# DC_DC_BOOST_CONVERTER_SOLAR.net
KiCad netlist of a schematic drawn in Altium Designer
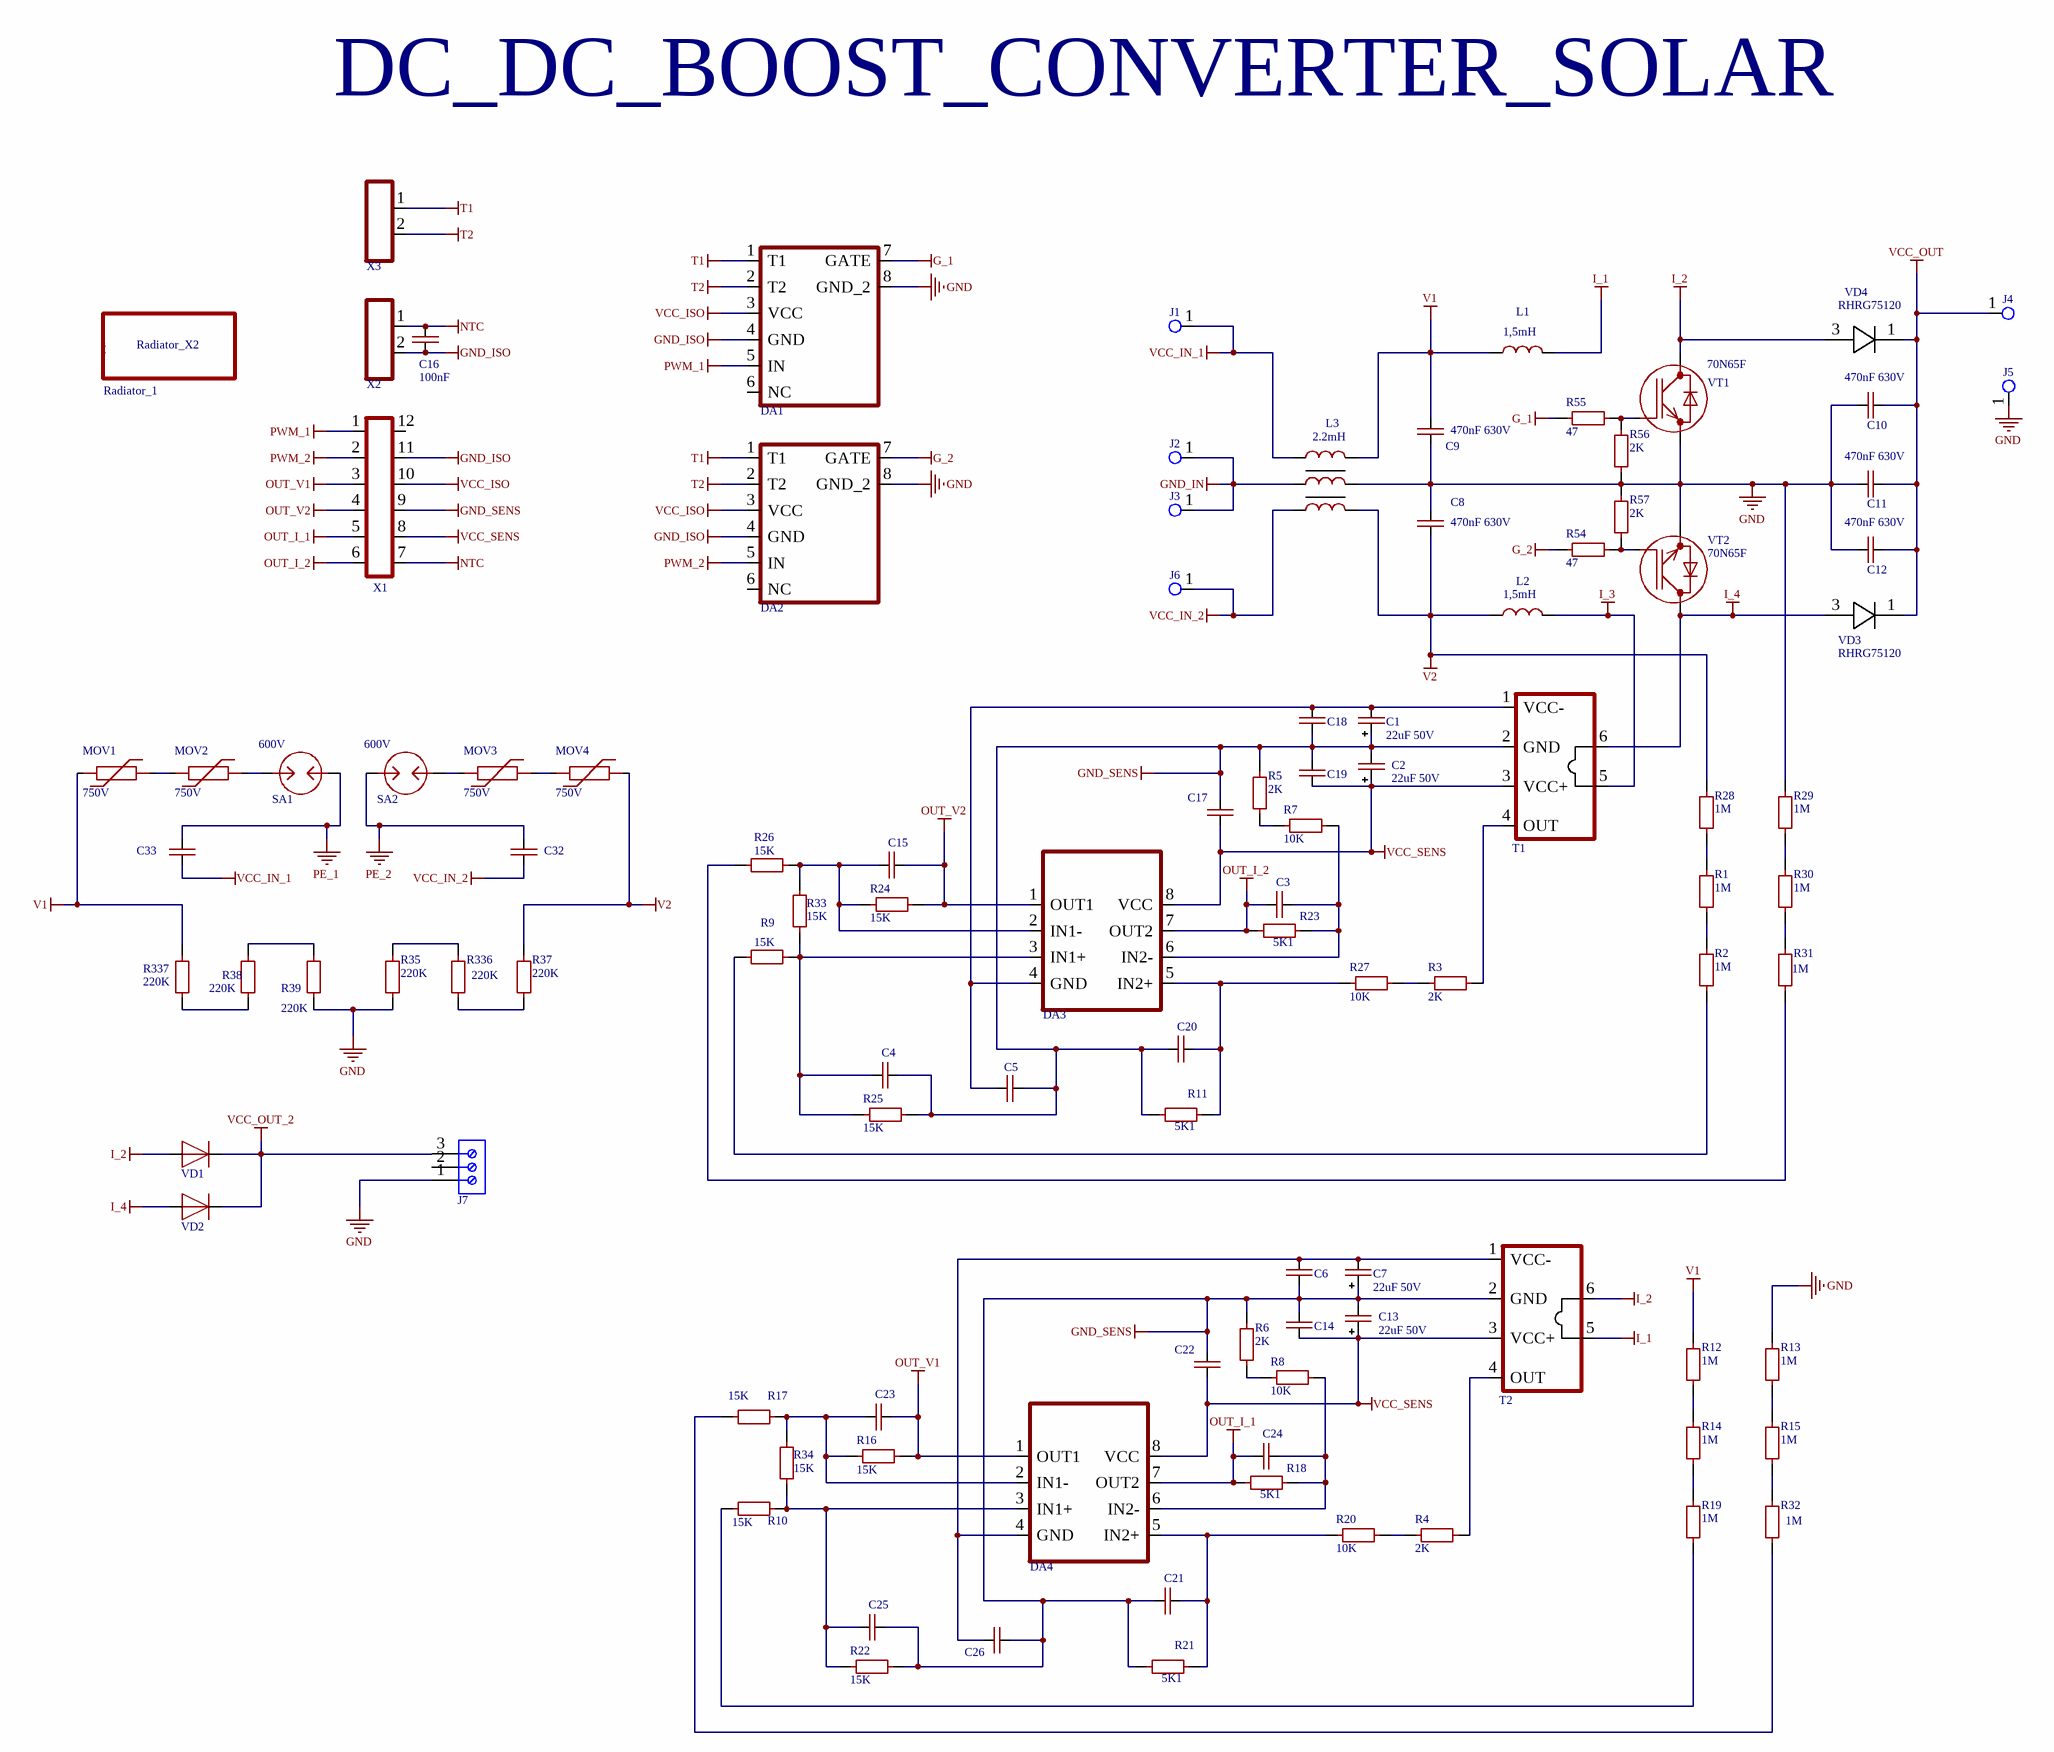
[diagram p0: DC_DC_BOOST_CONVERTER_SOLAR.SchDoc]

(export (version "E")
  (design (tool "Eeschema 10.0.6"))
  (components
    (comp (ref "C1")
      (value "22uF 50V")
      (footprint "CAPPOL_SMD_SIZE_E")
      (libsource (lib "PAS_COMPONENTS") (part "CAP-POLAR"))
    )
    (comp (ref "C2")
      (value "22uF 50V")
      (footprint "CAPPOL_SMD_SIZE_E")
      (libsource (lib "PAS_COMPONENTS") (part "CAP-POLAR"))
    )
    (comp (ref "C3")
      (value "~")
      (footprint "CAP-0805")
      (libsource (lib "PAS_COMPONENTS") (part "CAP-NON-POLAR"))
    )
    (comp (ref "C4")
      (value "~")
      (footprint "CAP-0805")
      (libsource (lib "PAS_COMPONENTS") (part "CAP-NON-POLAR"))
    )
    (comp (ref "C5")
      (value "~")
      (footprint "CAP-0805")
      (libsource (lib "PAS_COMPONENTS") (part "CAP-NON-POLAR"))
    )
    (comp (ref "C6")
      (value "~")
      (footprint "CAP-0805")
      (libsource (lib "PAS_COMPONENTS") (part "CAP-NON-POLAR"))
    )
    (comp (ref "C7")
      (value "22uF 50V")
      (footprint "CAPPOL_SMD_SIZE_E")
      (libsource (lib "PAS_COMPONENTS") (part "CAP-POLAR"))
    )
    (comp (ref "C8")
      (value "470nF 630V")
      (footprint "CAP-FILM-22.5X26.5X10")
      (libsource (lib "PAS_COMPONENTS") (part "CAP-NON-POLAR"))
    )
    (comp (ref "C9")
      (value "470nF 630V")
      (footprint "CAP-FILM-22.5X26.5X10")
      (libsource (lib "PAS_COMPONENTS") (part "CAP-NON-POLAR"))
    )
    (comp (ref "C10")
      (value "470nF 630V")
      (footprint "CAP-FILM-22.5X26.5X10")
      (libsource (lib "PAS_COMPONENTS") (part "CAP-NON-POLAR"))
    )
    (comp (ref "C11")
      (value "470nF 630V")
      (footprint "CAP-FILM-22.5X26.5X10")
      (libsource (lib "PAS_COMPONENTS") (part "CAP-NON-POLAR"))
    )
    (comp (ref "C12")
      (value "470nF 630V")
      (footprint "CAP-FILM-22.5X26.5X10")
      (libsource (lib "PAS_COMPONENTS") (part "CAP-NON-POLAR"))
    )
    (comp (ref "C13")
      (value "22uF 50V")
      (footprint "CAPPOL_SMD_SIZE_E")
      (libsource (lib "PAS_COMPONENTS") (part "CAP-POLAR"))
    )
    (comp (ref "C14")
      (value "~")
      (footprint "CAP-0805")
      (libsource (lib "PAS_COMPONENTS") (part "CAP-NON-POLAR"))
    )
    (comp (ref "C15")
      (value "~")
      (footprint "CAP-0805")
      (libsource (lib "PAS_COMPONENTS") (part "CAP-NON-POLAR"))
    )
    (comp (ref "C16")
      (value "100nF")
      (footprint "CAP-0805")
      (libsource (lib "PAS_COMPONENTS") (part "CAP-NON-POLAR"))
    )
    (comp (ref "C17")
      (value "~")
      (footprint "CAP-0805")
      (libsource (lib "PAS_COMPONENTS") (part "CAP-NON-POLAR"))
    )
    (comp (ref "C18")
      (value "~")
      (footprint "CAP-0805")
      (libsource (lib "PAS_COMPONENTS") (part "CAP-NON-POLAR"))
    )
    (comp (ref "C19")
      (value "~")
      (footprint "CAP-0805")
      (libsource (lib "PAS_COMPONENTS") (part "CAP-NON-POLAR"))
    )
    (comp (ref "C20")
      (value "~")
      (footprint "CAP-0805")
      (libsource (lib "PAS_COMPONENTS") (part "CAP-NON-POLAR"))
    )
    (comp (ref "C21")
      (value "~")
      (footprint "CAP-0805")
      (libsource (lib "PAS_COMPONENTS") (part "CAP-NON-POLAR"))
    )
    (comp (ref "C22")
      (value "~")
      (footprint "CAP-0805")
      (libsource (lib "PAS_COMPONENTS") (part "CAP-NON-POLAR"))
    )
    (comp (ref "C23")
      (value "~")
      (footprint "CAP-0805")
      (libsource (lib "PAS_COMPONENTS") (part "CAP-NON-POLAR"))
    )
    (comp (ref "C24")
      (value "~")
      (footprint "CAP-0805")
      (libsource (lib "PAS_COMPONENTS") (part "CAP-NON-POLAR"))
    )
    (comp (ref "C25")
      (value "~")
      (footprint "CAP-0805")
      (libsource (lib "PAS_COMPONENTS") (part "CAP-NON-POLAR"))
    )
    (comp (ref "C26")
      (value "~")
      (footprint "CAP-0805")
      (libsource (lib "PAS_COMPONENTS") (part "CAP-NON-POLAR"))
    )
    (comp (ref "C32") (value "~") (footprint "CAP-V") (libsource (lib "PASSIVE_COMPONENTS") (part "CAP-V")))
    (comp (ref "C33") (value "~") (footprint "CAP-V") (libsource (lib "PASSIVE_COMPONENTS") (part "CAP-V")))
    (comp (ref "DA1")
      (value "DRIVER_GATE_BOARD_solar_boost_converter")
      (footprint "DRIVER_GATE_BOARD_solar_boost_converter")
      (libsource (lib "DRIVER_GATE_BOARD_solar_boost_converter") (part "DRIVER_GATE_BOARD_solar_boost_converter"))
    )
    (comp (ref "DA2")
      (value "DRIVER_GATE_BOARD_solar_boost_converter")
      (footprint "DRIVER_GATE_BOARD_solar_boost_converter")
      (libsource (lib "DRIVER_GATE_BOARD_solar_boost_converter") (part "DRIVER_GATE_BOARD_solar_boost_converter"))
    )
    (comp (ref "DA3") (value "LM358") (footprint "SOIC8-150") (libsource (lib "LM358") (part "LM358")))
    (comp (ref "DA4") (value "LM358") (footprint "SOIC8-150") (libsource (lib "LM358") (part "LM358")))
    (comp (ref "J1")
      (value "~")
      (footprint "Klema_PCB_15A")
      (libsource (lib "Connectors") (part "Klema_15_A"))
    )
    (comp (ref "J2")
      (value "~")
      (footprint "Klema_PCB_15A")
      (libsource (lib "Connectors") (part "Klema_15_A"))
    )
    (comp (ref "J3")
      (value "~")
      (footprint "Klema_PCB_15A")
      (libsource (lib "Connectors") (part "Klema_15_A"))
    )
    (comp (ref "J4") (value "~") (footprint "Klema_PCB_15A") (libsource (lib "") (part "Klema_15_A_1")))
    (comp (ref "J5")
      (value "~")
      (footprint "Klema_PCB_15A")
      (libsource (lib "Connectors") (part "Klema_15_A"))
    )
    (comp (ref "J6")
      (value "~")
      (footprint "Klema_PCB_15A")
      (libsource (lib "Connectors") (part "Klema_15_A"))
    )
    (comp (ref "J7")
      (value "691101710003")
      (footprint "691101710003")
      (description "WR-TBL Series 101 Horizontal Entry Modular, THT, pitch 5mm, 3p")
      (fields (field (name "MANUFACTURER") "Wurth Elektronik"))
      (libsource (lib "Altium_WR-TBL (rev23d)") (part "691101710003"))
    )
    (comp (ref "L1")
      (value "1,5mH")
      (footprint "DROSSEL_TOR_50X30X20")
      (libsource (lib "DROSSEL_TOR_50X30X20") (part "IND-CONST"))
    )
    (comp (ref "L2")
      (value "1,5mH")
      (footprint "DROSSEL_TOR_50X30X20")
      (libsource (lib "DROSSEL_TOR_50X30X20") (part "IND-CONST"))
    )
    (comp (ref "L3")
      (value "2.2mH")
      (footprint "DROSSEL_TOR_50X30X20X3")
      (libsource (lib "DROSSEL_TOR_50X30X20X3") (part "IND-CONST"))
    )
    (comp (ref "MOV1")
      (value "750V")
      (footprint "VARISTOR_20MM")
      (libsource (lib "VARISTOR") (part "VARISTOR"))
    )
    (comp (ref "MOV2")
      (value "750V")
      (footprint "VARISTOR_20MM")
      (libsource (lib "VARISTOR") (part "VARISTOR"))
    )
    (comp (ref "MOV3")
      (value "750V")
      (footprint "VARISTOR_20MM")
      (libsource (lib "VARISTOR") (part "VARISTOR"))
    )
    (comp (ref "MOV4")
      (value "750V")
      (footprint "VARISTOR_20MM")
      (libsource (lib "VARISTOR") (part "VARISTOR"))
    )
    (comp (ref "R1")
      (value "1M")
      (footprint "RES-1206")
      (libsource (lib "PAS_COMPONENTS") (part "RES-CONST"))
    )
    (comp (ref "R2")
      (value "1M")
      (footprint "RES-1206")
      (libsource (lib "PAS_COMPONENTS") (part "RES-CONST"))
    )
    (comp (ref "R3")
      (value "2K")
      (footprint "RES-0805")
      (libsource (lib "PAS_COMPONENTS") (part "RES-CONST"))
    )
    (comp (ref "R4")
      (value "2K")
      (footprint "RES-0805")
      (libsource (lib "PAS_COMPONENTS") (part "RES-CONST"))
    )
    (comp (ref "R5")
      (value "2K")
      (footprint "RES-0805")
      (libsource (lib "PAS_COMPONENTS") (part "RES-CONST"))
    )
    (comp (ref "R6")
      (value "2K")
      (footprint "RES-0805")
      (libsource (lib "PAS_COMPONENTS") (part "RES-CONST"))
    )
    (comp (ref "R7")
      (value "10K")
      (footprint "RES-0805")
      (libsource (lib "PAS_COMPONENTS") (part "RES-CONST"))
    )
    (comp (ref "R8")
      (value "10K")
      (footprint "RES-0805")
      (libsource (lib "PAS_COMPONENTS") (part "RES-CONST"))
    )
    (comp (ref "R9")
      (value "15K")
      (footprint "RES-0805")
      (libsource (lib "PAS_COMPONENTS") (part "RES-CONST"))
    )
    (comp (ref "R10")
      (value "15K")
      (footprint "RES-0805")
      (libsource (lib "PAS_COMPONENTS") (part "RES-CONST"))
    )
    (comp (ref "R11")
      (value "5K1")
      (footprint "RES-0805")
      (libsource (lib "PAS_COMPONENTS") (part "RES-CONST"))
    )
    (comp (ref "R12")
      (value "1M")
      (footprint "RES-1206")
      (libsource (lib "PAS_COMPONENTS") (part "RES-CONST"))
    )
    (comp (ref "R13")
      (value "1M")
      (footprint "RES-1206")
      (libsource (lib "PAS_COMPONENTS") (part "RES-CONST"))
    )
    (comp (ref "R14")
      (value "1M")
      (footprint "RES-1206")
      (libsource (lib "PAS_COMPONENTS") (part "RES-CONST"))
    )
    (comp (ref "R15")
      (value "1M")
      (footprint "RES-1206")
      (libsource (lib "PAS_COMPONENTS") (part "RES-CONST"))
    )
    (comp (ref "R16")
      (value "15K")
      (footprint "RES-0805")
      (libsource (lib "PAS_COMPONENTS") (part "RES-CONST"))
    )
    (comp (ref "R17")
      (value "15K")
      (footprint "RES-0805")
      (libsource (lib "PAS_COMPONENTS") (part "RES-CONST"))
    )
    (comp (ref "R18")
      (value "5K1")
      (footprint "RES-0805")
      (libsource (lib "PAS_COMPONENTS") (part "RES-CONST"))
    )
    (comp (ref "R19")
      (value "1M")
      (footprint "RES-1206")
      (libsource (lib "PAS_COMPONENTS") (part "RES-CONST"))
    )
    (comp (ref "R20")
      (value "10K")
      (footprint "RES-0805")
      (libsource (lib "PAS_COMPONENTS") (part "RES-CONST"))
    )
    (comp (ref "R21")
      (value "5K1")
      (footprint "RES-0805")
      (libsource (lib "PAS_COMPONENTS") (part "RES-CONST"))
    )
    (comp (ref "R22")
      (value "15K")
      (footprint "RES-0805")
      (libsource (lib "PAS_COMPONENTS") (part "RES-CONST"))
    )
    (comp (ref "R23")
      (value "5K1")
      (footprint "RES-0805")
      (libsource (lib "PAS_COMPONENTS") (part "RES-CONST"))
    )
    (comp (ref "R24")
      (value "15K")
      (footprint "RES-0805")
      (libsource (lib "PAS_COMPONENTS") (part "RES-CONST"))
    )
    (comp (ref "R25")
      (value "15K")
      (footprint "RES-0805")
      (libsource (lib "PAS_COMPONENTS") (part "RES-CONST"))
    )
    (comp (ref "R26")
      (value "15K")
      (footprint "RES-0805")
      (libsource (lib "PAS_COMPONENTS") (part "RES-CONST"))
    )
    (comp (ref "R27")
      (value "10K")
      (footprint "RES-0805")
      (libsource (lib "PAS_COMPONENTS") (part "RES-CONST"))
    )
    (comp (ref "R28")
      (value "1M")
      (footprint "RES-1206")
      (libsource (lib "PAS_COMPONENTS") (part "RES-CONST"))
    )
    (comp (ref "R29")
      (value "1M")
      (footprint "RES-1206")
      (libsource (lib "PAS_COMPONENTS") (part "RES-CONST"))
    )
    (comp (ref "R30")
      (value "1M")
      (footprint "RES-1206")
      (libsource (lib "PAS_COMPONENTS") (part "RES-CONST"))
    )
    (comp (ref "R31")
      (value "1M")
      (footprint "RES-1206")
      (libsource (lib "PAS_COMPONENTS") (part "RES-CONST"))
    )
    (comp (ref "R32")
      (value "1M")
      (footprint "RES-1206")
      (libsource (lib "PAS_COMPONENTS") (part "RES-CONST"))
    )
    (comp (ref "R33")
      (value "15K")
      (footprint "RES-0805")
      (libsource (lib "PAS_COMPONENTS") (part "RES-CONST"))
    )
    (comp (ref "R34")
      (value "15K")
      (footprint "RES-0805")
      (libsource (lib "PAS_COMPONENTS") (part "RES-CONST"))
    )
    (comp (ref "R35")
      (value "220K")
      (footprint "RES-1206")
      (libsource (lib "PAS_COMPONENTS") (part "RES-CONST"))
    )
    (comp (ref "R37")
      (value "220K")
      (footprint "RES-1206")
      (libsource (lib "PAS_COMPONENTS") (part "RES-CONST"))
    )
    (comp (ref "R38")
      (value "220K")
      (footprint "RES-1206")
      (libsource (lib "PAS_COMPONENTS") (part "RES-CONST"))
    )
    (comp (ref "R39")
      (value "220K")
      (footprint "RES-1206")
      (libsource (lib "PAS_COMPONENTS") (part "RES-CONST"))
    )
    (comp (ref "R54")
      (value "47")
      (footprint "RES-1206")
      (libsource (lib "PAS_COMPONENTS") (part "RES-CONST"))
    )
    (comp (ref "R55")
      (value "47")
      (footprint "RES-1206")
      (libsource (lib "PAS_COMPONENTS") (part "RES-CONST"))
    )
    (comp (ref "R56")
      (value "2K")
      (footprint "RES-1206")
      (libsource (lib "PAS_COMPONENTS") (part "RES-CONST"))
    )
    (comp (ref "R57")
      (value "2K")
      (footprint "RES-1206")
      (libsource (lib "PAS_COMPONENTS") (part "RES-CONST"))
    )
    (comp (ref "R336")
      (value "220K")
      (footprint "RES-1206")
      (libsource (lib "PAS_COMPONENTS") (part "RES-CONST"))
    )
    (comp (ref "R337")
      (value "220K")
      (footprint "RES-1206")
      (libsource (lib "PAS_COMPONENTS") (part "RES-CONST"))
    )
    (comp (ref "Radiator_1")
      (value "Radiator_X2")
      (footprint "Radiator_X2")
      (libsource (lib "Radiator_X2") (part "Radiator_X2"))
    )
    (comp (ref "SA1") (value "600V") (footprint "SPARK_GAP") (libsource (lib "SPARK_GAP") (part "SPARK_GAP")))
    (comp (ref "SA2") (value "600V") (footprint "SPARK_GAP") (libsource (lib "SPARK_GAP") (part "SPARK_GAP")))
    (comp (ref "T1")
      (value "STB-HAA20")
      (footprint "STB-HAA20")
      (libsource (lib "STB-HAA20") (part "STB-HAA20"))
    )
    (comp (ref "T2")
      (value "STB-HAA20")
      (footprint "STB-HAA20")
      (libsource (lib "STB-HAA20") (part "STB-HAA20"))
    )
    (comp (ref "VD1") (value "DIODE") (footprint "DIODE_R6") (libsource (lib "DIODE_R6") (part "DIODE")))
    (comp (ref "VD2") (value "DIODE") (footprint "DIODE_R6") (libsource (lib "DIODE_R6") (part "DIODE")))
    (comp (ref "VD3") (value "RHRG75120") (footprint "TO-247-2") (libsource (lib "Diodes") (part "MUR4060")))
    (comp (ref "VD4") (value "RHRG75120") (footprint "TO-247-2") (libsource (lib "Diodes") (part "MUR4060")))
    (comp (ref "VT1")
      (value "70N65F")
      (footprint "TO-247-3")
      (libsource (lib "TRANSISTORS") (part "IGBT-N-GCE"))
    )
    (comp (ref "VT2")
      (value "70N65F")
      (footprint "TO-247-3")
      (libsource (lib "TRANSISTORS") (part "IGBT-N-GCE"))
    )
    (comp (ref "X1")
      (value "CONN_IDC_12_PIN2.54")
      (footprint "CONN_IDC_12_PIN2.54")
      (libsource (lib "CONN_IDC_12_PIN2.54") (part "CONN_IDC_12_PIN2.54"))
    )
    (comp (ref "X2") (value "CONN-2-PIN") (footprint "XH2-") (libsource (lib "XH 2PIN") (part "CONN-2-PIN")))
    (comp (ref "X3") (value "CONN-2-PIN") (footprint "XH2-") (libsource (lib "XH 2PIN") (part "CONN-2-PIN")))
  )
  (nets
    (net (code "1") (name "GND") (class "Default")
      (node (ref "C10") (pin "1") (pinfunction "1_1") (pintype "passive"))
      (node (ref "C11") (pin "1") (pinfunction "1_1") (pintype "passive"))
      (node (ref "C12") (pin "1") (pinfunction "1_1") (pintype "passive"))
      (node (ref "C8") (pin "1") (pinfunction "1_1") (pintype "passive"))
      (node (ref "C9") (pin "2") (pinfunction "2_2") (pintype "passive"))
      (node (ref "DA1") (pin "8") (pinfunction "GND_2_8") (pintype "passive"))
      (node (ref "DA2") (pin "8") (pinfunction "GND_2_8") (pintype "passive"))
      (node (ref "J5") (pin "1") (pinfunction "0_1") (pintype "passive"))
      (node (ref "J7") (pin "1") (pinfunction "1_1") (pintype "passive"))
      (node (ref "L3") (pin "4") (pinfunction "4_4") (pintype "passive"))
      (node (ref "R13") (pin "1") (pinfunction "1_1") (pintype "passive"))
      (node (ref "R29") (pin "1") (pinfunction "1_1") (pintype "passive"))
      (node (ref "R35") (pin "2") (pinfunction "2_2") (pintype "passive"))
      (node (ref "R39") (pin "2") (pinfunction "2_2") (pintype "passive"))
      (node (ref "R56") (pin "2") (pinfunction "2_2") (pintype "passive"))
      (node (ref "R57") (pin "1") (pinfunction "1_1") (pintype "passive"))
      (node (ref "VT1") (pin "3") (pinfunction "E_3") (pintype "passive"))
      (node (ref "VT2") (pin "3") (pinfunction "E_3") (pintype "passive"))
    )
    (net (code "2") (name "GND_IN") (class "Default")
      (node (ref "J2") (pin "1") (pinfunction "0_1") (pintype "passive"))
      (node (ref "J3") (pin "1") (pinfunction "0_1") (pintype "passive"))
      (node (ref "L3") (pin "3") (pinfunction "3_3") (pintype "passive"))
    )
    (net (code "3") (name "GND_ISO") (class "Default")
      (node (ref "C16") (pin "2") (pinfunction "2_2") (pintype "passive"))
      (node (ref "DA1") (pin "4") (pinfunction "GND_4") (pintype "passive"))
      (node (ref "DA2") (pin "4") (pinfunction "GND_4") (pintype "passive"))
      (node (ref "X1") (pin "11") (pinfunction "11_11") (pintype "passive"))
      (node (ref "X2") (pin "2") (pinfunction "2_2") (pintype "passive"))
    )
    (net (code "4") (name "GND_SENS") (class "Default")
      (node (ref "C1") (pin "1") (pinfunction "+_1") (pintype "passive"))
      (node (ref "C13") (pin "2") (pinfunction "-_2") (pintype "passive"))
      (node (ref "C14") (pin "2") (pinfunction "2_2") (pintype "passive"))
      (node (ref "C17") (pin "2") (pinfunction "2_2") (pintype "passive"))
      (node (ref "C18") (pin "1") (pinfunction "1_1") (pintype "passive"))
      (node (ref "C19") (pin "2") (pinfunction "2_2") (pintype "passive"))
      (node (ref "C2") (pin "2") (pinfunction "-_2") (pintype "passive"))
      (node (ref "C20") (pin "1") (pinfunction "1_1") (pintype "passive"))
      (node (ref "C21") (pin "1") (pinfunction "1_1") (pintype "passive"))
      (node (ref "C22") (pin "2") (pinfunction "2_2") (pintype "passive"))
      (node (ref "C25") (pin "1") (pinfunction "1_1") (pintype "passive"))
      (node (ref "C26") (pin "2") (pinfunction "2_2") (pintype "passive"))
      (node (ref "C4") (pin "1") (pinfunction "1_1") (pintype "passive"))
      (node (ref "C5") (pin "2") (pinfunction "2_2") (pintype "passive"))
      (node (ref "C6") (pin "1") (pinfunction "1_1") (pintype "passive"))
      (node (ref "C7") (pin "1") (pinfunction "+_1") (pintype "passive"))
      (node (ref "R11") (pin "1") (pinfunction "1_1") (pintype "passive"))
      (node (ref "R21") (pin "1") (pinfunction "1_1") (pintype "passive"))
      (node (ref "R22") (pin "2") (pinfunction "2_2") (pintype "passive"))
      (node (ref "R25") (pin "2") (pinfunction "2_2") (pintype "passive"))
      (node (ref "R5") (pin "1") (pinfunction "1_1") (pintype "passive"))
      (node (ref "R6") (pin "1") (pinfunction "1_1") (pintype "passive"))
      (node (ref "T1") (pin "2") (pinfunction "GND_2") (pintype "passive"))
      (node (ref "T2") (pin "2") (pinfunction "GND_2") (pintype "passive"))
      (node (ref "X1") (pin "9") (pinfunction "9_9") (pintype "passive"))
    )
    (net (code "5") (name "G_1") (class "Default")
      (node (ref "DA1") (pin "7") (pinfunction "GATE_7") (pintype "passive"))
      (node (ref "R55") (pin "2") (pinfunction "2_2") (pintype "passive"))
    )
    (net (code "6") (name "G_2") (class "Default")
      (node (ref "DA2") (pin "7") (pinfunction "GATE_7") (pintype "passive"))
      (node (ref "R54") (pin "2") (pinfunction "2_2") (pintype "passive"))
    )
    (net (code "7") (name "I_1") (class "Default")
      (node (ref "L1") (pin "2") (pinfunction "2_2") (pintype "passive"))
      (node (ref "T2") (pin "5") (pintype "passive"))
    )
    (net (code "8") (name "I_2") (class "Default")
      (node (ref "T2") (pin "6") (pintype "passive"))
      (node (ref "VD1") (pin "2") (pinfunction "A_2") (pintype "passive"))
      (node (ref "VD4") (pin "3") (pinfunction "3_3") (pintype "passive"))
      (node (ref "VT1") (pin "2") (pinfunction "C_2") (pintype "passive"))
    )
    (net (code "9") (name "I_3") (class "Default")
      (node (ref "L2") (pin "2") (pinfunction "2_2") (pintype "passive"))
      (node (ref "T1") (pin "5") (pintype "passive"))
    )
    (net (code "10") (name "I_4") (class "Default")
      (node (ref "T1") (pin "6") (pintype "passive"))
      (node (ref "VD2") (pin "2") (pinfunction "A_2") (pintype "passive"))
      (node (ref "VD3") (pin "3") (pinfunction "3_3") (pintype "passive"))
      (node (ref "VT2") (pin "2") (pinfunction "C_2") (pintype "passive"))
    )
    (net (code "11") (name "NTC") (class "Default")
      (node (ref "C16") (pin "1") (pinfunction "1_1") (pintype "passive"))
      (node (ref "X1") (pin "7") (pinfunction "7_7") (pintype "passive"))
      (node (ref "X2") (pin "1") (pinfunction "1_1") (pintype "passive"))
    )
    (net (code "12") (name "Net-(C1--)") (class "Default")
      (node (ref "C1") (pin "2") (pinfunction "-_2") (pintype "passive"))
      (node (ref "C18") (pin "2") (pinfunction "2_2") (pintype "passive"))
      (node (ref "C5") (pin "1") (pinfunction "1_1") (pintype "passive"))
      (node (ref "DA3") (pin "4") (pinfunction "GND_4") (pintype "passive"))
      (node (ref "T1") (pin "1") (pinfunction "VCC-_1") (pintype "passive"))
    )
    (net (code "13") (name "Net-(C7--)") (class "Default")
      (node (ref "C26") (pin "1") (pinfunction "1_1") (pintype "passive"))
      (node (ref "C6") (pin "2") (pinfunction "2_2") (pintype "passive"))
      (node (ref "C7") (pin "2") (pinfunction "-_2") (pintype "passive"))
      (node (ref "DA4") (pin "4") (pinfunction "GND_4") (pintype "passive"))
      (node (ref "T2") (pin "1") (pinfunction "VCC-_1") (pintype "passive"))
    )
    (net (code "14") (name "Net-(DA3-IN1+)") (class "Default")
      (node (ref "C4") (pin "2") (pinfunction "2_2") (pintype "passive"))
      (node (ref "DA3") (pin "3") (pinfunction "IN1+_3") (pintype "passive"))
      (node (ref "R25") (pin "1") (pinfunction "1_1") (pintype "passive"))
      (node (ref "R33") (pin "1") (pinfunction "1_1") (pintype "passive"))
      (node (ref "R9") (pin "1") (pinfunction "1_1") (pintype "passive"))
    )
    (net (code "15") (name "Net-(DA3-IN1-)") (class "Default")
      (node (ref "C15") (pin "2") (pinfunction "2_2") (pintype "passive"))
      (node (ref "DA3") (pin "2") (pinfunction "IN1-_2") (pintype "passive"))
      (node (ref "R24") (pin "1") (pinfunction "1_1") (pintype "passive"))
      (node (ref "R26") (pin "1") (pinfunction "1_1") (pintype "passive"))
      (node (ref "R33") (pin "2") (pinfunction "2_2") (pintype "passive"))
    )
    (net (code "16") (name "Net-(DA3-IN2+)") (class "Default")
      (node (ref "C20") (pin "2") (pinfunction "2_2") (pintype "passive"))
      (node (ref "DA3") (pin "5") (pinfunction "IN2+_5") (pintype "passive"))
      (node (ref "R11") (pin "2") (pinfunction "2_2") (pintype "passive"))
      (node (ref "R27") (pin "2") (pinfunction "2_2") (pintype "passive"))
    )
    (net (code "17") (name "Net-(DA3-IN2-)") (class "Default")
      (node (ref "C3") (pin "1") (pinfunction "1_1") (pintype "passive"))
      (node (ref "DA3") (pin "6") (pinfunction "IN2-_6") (pintype "passive"))
      (node (ref "R23") (pin "2") (pinfunction "2_2") (pintype "passive"))
      (node (ref "R7") (pin "2") (pinfunction "2_2") (pintype "passive"))
    )
    (net (code "18") (name "Net-(DA4-IN1+)") (class "Default")
      (node (ref "C25") (pin "2") (pinfunction "2_2") (pintype "passive"))
      (node (ref "DA4") (pin "3") (pinfunction "IN1+_3") (pintype "passive"))
      (node (ref "R10") (pin "1") (pinfunction "1_1") (pintype "passive"))
      (node (ref "R22") (pin "1") (pinfunction "1_1") (pintype "passive"))
      (node (ref "R34") (pin "1") (pinfunction "1_1") (pintype "passive"))
    )
    (net (code "19") (name "Net-(DA4-IN1-)") (class "Default")
      (node (ref "C23") (pin "2") (pinfunction "2_2") (pintype "passive"))
      (node (ref "DA4") (pin "2") (pinfunction "IN1-_2") (pintype "passive"))
      (node (ref "R16") (pin "1") (pinfunction "1_1") (pintype "passive"))
      (node (ref "R17") (pin "1") (pinfunction "1_1") (pintype "passive"))
      (node (ref "R34") (pin "2") (pinfunction "2_2") (pintype "passive"))
    )
    (net (code "20") (name "Net-(DA4-IN2+)") (class "Default")
      (node (ref "C21") (pin "2") (pinfunction "2_2") (pintype "passive"))
      (node (ref "DA4") (pin "5") (pinfunction "IN2+_5") (pintype "passive"))
      (node (ref "R20") (pin "2") (pinfunction "2_2") (pintype "passive"))
      (node (ref "R21") (pin "2") (pinfunction "2_2") (pintype "passive"))
    )
    (net (code "21") (name "Net-(DA4-IN2-)") (class "Default")
      (node (ref "C24") (pin "1") (pinfunction "1_1") (pintype "passive"))
      (node (ref "DA4") (pin "6") (pinfunction "IN2-_6") (pintype "passive"))
      (node (ref "R18") (pin "2") (pinfunction "2_2") (pintype "passive"))
      (node (ref "R8") (pin "2") (pinfunction "2_2") (pintype "passive"))
    )
    (net (code "22") (name "Net-(MOV1-Pad2)") (class "Default")
      (node (ref "MOV1") (pin "2") (pinfunction "2_2") (pintype "passive"))
      (node (ref "MOV2") (pin "1") (pinfunction "1_1") (pintype "passive"))
    )
    (net (code "23") (name "Net-(MOV2-Pad2)") (class "Default")
      (node (ref "MOV2") (pin "2") (pinfunction "2_2") (pintype "passive"))
      (node (ref "SA1") (pin "1") (pinfunction "1_1") (pintype "passive"))
    )
    (net (code "24") (name "Net-(MOV3-Pad1)") (class "Default")
      (node (ref "MOV3") (pin "1") (pinfunction "1_1") (pintype "passive"))
      (node (ref "SA2") (pin "2") (pinfunction "2_2") (pintype "passive"))
    )
    (net (code "25") (name "Net-(MOV3-Pad2)") (class "Default")
      (node (ref "MOV3") (pin "2") (pinfunction "2_2") (pintype "passive"))
      (node (ref "MOV4") (pin "1") (pinfunction "1_1") (pintype "passive"))
    )
    (net (code "26") (name "Net-(R1-Pad1)") (class "Default")
      (node (ref "R1") (pin "1") (pinfunction "1_1") (pintype "passive"))
      (node (ref "R28") (pin "2") (pinfunction "2_2") (pintype "passive"))
    )
    (net (code "27") (name "Net-(R1-Pad2)") (class "Default")
      (node (ref "R1") (pin "2") (pinfunction "2_2") (pintype "passive"))
      (node (ref "R2") (pin "1") (pinfunction "1_1") (pintype "passive"))
    )
    (net (code "28") (name "Net-(R2-Pad2)") (class "Default")
      (node (ref "R2") (pin "2") (pinfunction "2_2") (pintype "passive"))
      (node (ref "R9") (pin "2") (pinfunction "2_2") (pintype "passive"))
    )
    (net (code "29") (name "Net-(R5-Pad2)") (class "Default")
      (node (ref "R5") (pin "2") (pinfunction "2_2") (pintype "passive"))
      (node (ref "R7") (pin "1") (pinfunction "1_1") (pintype "passive"))
    )
    (net (code "30") (name "Net-(R6-Pad2)") (class "Default")
      (node (ref "R6") (pin "2") (pinfunction "2_2") (pintype "passive"))
      (node (ref "R8") (pin "1") (pinfunction "1_1") (pintype "passive"))
    )
    (net (code "31") (name "Net-(R10-Pad2)") (class "Default")
      (node (ref "R10") (pin "2") (pinfunction "2_2") (pintype "passive"))
      (node (ref "R19") (pin "2") (pinfunction "2_2") (pintype "passive"))
    )
    (net (code "32") (name "Net-(R12-Pad2)") (class "Default")
      (node (ref "R12") (pin "2") (pinfunction "2_2") (pintype "passive"))
      (node (ref "R14") (pin "1") (pinfunction "1_1") (pintype "passive"))
    )
    (net (code "33") (name "Net-(R13-Pad2)") (class "Default")
      (node (ref "R13") (pin "2") (pinfunction "2_2") (pintype "passive"))
      (node (ref "R15") (pin "1") (pinfunction "1_1") (pintype "passive"))
    )
    (net (code "34") (name "Net-(R14-Pad2)") (class "Default")
      (node (ref "R14") (pin "2") (pinfunction "2_2") (pintype "passive"))
      (node (ref "R19") (pin "1") (pinfunction "1_1") (pintype "passive"))
    )
    (net (code "35") (name "Net-(R15-Pad2)") (class "Default")
      (node (ref "R15") (pin "2") (pinfunction "2_2") (pintype "passive"))
      (node (ref "R32") (pin "1") (pinfunction "1_1") (pintype "passive"))
    )
    (net (code "36") (name "Net-(R17-Pad2)") (class "Default")
      (node (ref "R17") (pin "2") (pinfunction "2_2") (pintype "passive"))
      (node (ref "R32") (pin "2") (pinfunction "2_2") (pintype "passive"))
    )
    (net (code "37") (name "Net-(R20-Pad1)") (class "Default")
      (node (ref "R20") (pin "1") (pinfunction "1_1") (pintype "passive"))
      (node (ref "R4") (pin "2") (pinfunction "2_2") (pintype "passive"))
    )
    (net (code "38") (name "Net-(R26-Pad2)") (class "Default")
      (node (ref "R26") (pin "2") (pinfunction "2_2") (pintype "passive"))
      (node (ref "R31") (pin "2") (pinfunction "2_2") (pintype "passive"))
    )
    (net (code "39") (name "Net-(R27-Pad1)") (class "Default")
      (node (ref "R27") (pin "1") (pinfunction "1_1") (pintype "passive"))
      (node (ref "R3") (pin "2") (pinfunction "2_2") (pintype "passive"))
    )
    (net (code "40") (name "Net-(R29-Pad2)") (class "Default")
      (node (ref "R29") (pin "2") (pinfunction "2_2") (pintype "passive"))
      (node (ref "R30") (pin "1") (pinfunction "1_1") (pintype "passive"))
    )
    (net (code "41") (name "Net-(R30-Pad2)") (class "Default")
      (node (ref "R30") (pin "2") (pinfunction "2_2") (pintype "passive"))
      (node (ref "R31") (pin "1") (pinfunction "1_1") (pintype "passive"))
    )
    (net (code "42") (name "Net-(R38-Pad1)") (class "Default")
      (node (ref "R38") (pin "1") (pinfunction "1_1") (pintype "passive"))
      (node (ref "R39") (pin "1") (pinfunction "1_1") (pintype "passive"))
    )
    (net (code "43") (name "Net-(R336-Pad1)") (class "Default")
      (node (ref "R336") (pin "1") (pinfunction "1_1") (pintype "passive"))
      (node (ref "R35") (pin "1") (pinfunction "1_1") (pintype "passive"))
    )
    (net (code "44") (name "Net-(R336-Pad2)") (class "Default")
      (node (ref "R336") (pin "2") (pinfunction "2_2") (pintype "passive"))
      (node (ref "R37") (pin "2") (pinfunction "2_2") (pintype "passive"))
    )
    (net (code "45") (name "Net-(R337-Pad2)") (class "Default")
      (node (ref "R337") (pin "2") (pinfunction "2_2") (pintype "passive"))
      (node (ref "R38") (pin "2") (pinfunction "2_2") (pintype "passive"))
    )
    (net (code "46") (name "Net-(T1-OUT)") (class "Default")
      (node (ref "R3") (pin "1") (pinfunction "1_1") (pintype "passive"))
      (node (ref "T1") (pin "4") (pinfunction "OUT_4") (pintype "passive"))
    )
    (net (code "47") (name "Net-(T2-OUT)") (class "Default")
      (node (ref "R4") (pin "1") (pinfunction "1_1") (pintype "passive"))
      (node (ref "T2") (pin "4") (pinfunction "OUT_4") (pintype "passive"))
    )
    (net (code "48") (name "Net-(VT1-G)") (class "Default")
      (node (ref "R55") (pin "1") (pinfunction "1_1") (pintype "passive"))
      (node (ref "R56") (pin "1") (pinfunction "1_1") (pintype "passive"))
      (node (ref "VT1") (pin "1") (pinfunction "G_1") (pintype "passive"))
    )
    (net (code "49") (name "Net-(VT2-G)") (class "Default")
      (node (ref "R54") (pin "1") (pinfunction "1_1") (pintype "passive"))
      (node (ref "R57") (pin "2") (pinfunction "2_2") (pintype "passive"))
      (node (ref "VT2") (pin "1") (pinfunction "G_1") (pintype "passive"))
    )
    (net (code "50") (name "OUT_I_1") (class "Default")
      (node (ref "C24") (pin "2") (pinfunction "2_2") (pintype "passive"))
      (node (ref "DA4") (pin "7") (pinfunction "OUT2_7") (pintype "passive"))
      (node (ref "R18") (pin "1") (pinfunction "1_1") (pintype "passive"))
      (node (ref "X1") (pin "5") (pinfunction "5_5") (pintype "passive"))
    )
    (net (code "51") (name "OUT_I_2") (class "Default")
      (node (ref "C3") (pin "2") (pinfunction "2_2") (pintype "passive"))
      (node (ref "DA3") (pin "7") (pinfunction "OUT2_7") (pintype "passive"))
      (node (ref "R23") (pin "1") (pinfunction "1_1") (pintype "passive"))
      (node (ref "X1") (pin "6") (pinfunction "6_6") (pintype "passive"))
    )
    (net (code "52") (name "OUT_V1") (class "Default")
      (node (ref "C23") (pin "1") (pinfunction "1_1") (pintype "passive"))
      (node (ref "DA4") (pin "1") (pinfunction "OUT1_1") (pintype "passive"))
      (node (ref "R16") (pin "2") (pinfunction "2_2") (pintype "passive"))
      (node (ref "X1") (pin "3") (pinfunction "3_3") (pintype "passive"))
    )
    (net (code "53") (name "OUT_V2") (class "Default")
      (node (ref "C15") (pin "1") (pinfunction "1_1") (pintype "passive"))
      (node (ref "DA3") (pin "1") (pinfunction "OUT1_1") (pintype "passive"))
      (node (ref "R24") (pin "2") (pinfunction "2_2") (pintype "passive"))
      (node (ref "X1") (pin "4") (pinfunction "4_4") (pintype "passive"))
    )
    (net (code "54") (name "PE_1") (class "Default")
      (node (ref "C33") (pin "1") (pinfunction "1_1") (pintype "passive"))
      (node (ref "SA1") (pin "2") (pinfunction "2_2") (pintype "passive"))
    )
    (net (code "55") (name "PE_2") (class "Default")
      (node (ref "C32") (pin "2") (pinfunction "2_2") (pintype "passive"))
      (node (ref "SA2") (pin "1") (pinfunction "1_1") (pintype "passive"))
    )
    (net (code "56") (name "PWM_1") (class "Default")
      (node (ref "DA1") (pin "5") (pinfunction "IN_5") (pintype "passive"))
      (node (ref "X1") (pin "1") (pinfunction "1_1") (pintype "passive"))
    )
    (net (code "57") (name "PWM_2") (class "Default")
      (node (ref "DA2") (pin "5") (pinfunction "IN_5") (pintype "passive"))
      (node (ref "X1") (pin "2") (pinfunction "2_2") (pintype "passive"))
    )
    (net (code "58") (name "T1") (class "Default")
      (node (ref "DA1") (pin "1") (pinfunction "T1_1") (pintype "passive"))
      (node (ref "DA2") (pin "1") (pinfunction "T1_1") (pintype "passive"))
      (node (ref "X3") (pin "1") (pinfunction "1_1") (pintype "passive"))
    )
    (net (code "59") (name "T2") (class "Default")
      (node (ref "DA1") (pin "2") (pinfunction "T2_2") (pintype "passive"))
      (node (ref "DA2") (pin "2") (pinfunction "T2_2") (pintype "passive"))
      (node (ref "X3") (pin "2") (pinfunction "2_2") (pintype "passive"))
    )
    (net (code "60") (name "V1") (class "Default")
      (node (ref "C9") (pin "1") (pinfunction "1_1") (pintype "passive"))
      (node (ref "L1") (pin "1") (pinfunction "1_1") (pintype "passive"))
      (node (ref "L3") (pin "2") (pinfunction "2_2") (pintype "passive"))
      (node (ref "MOV1") (pin "1") (pinfunction "1_1") (pintype "passive"))
      (node (ref "R12") (pin "1") (pinfunction "1_1") (pintype "passive"))
      (node (ref "R337") (pin "1") (pinfunction "1_1") (pintype "passive"))
    )
    (net (code "61") (name "V2") (class "Default")
      (node (ref "C8") (pin "2") (pinfunction "2_2") (pintype "passive"))
      (node (ref "L2") (pin "1") (pinfunction "1_1") (pintype "passive"))
      (node (ref "L3") (pin "6") (pinfunction "6_6") (pintype "passive"))
      (node (ref "MOV4") (pin "2") (pinfunction "2_2") (pintype "passive"))
      (node (ref "R28") (pin "1") (pinfunction "1_1") (pintype "passive"))
      (node (ref "R37") (pin "1") (pinfunction "1_1") (pintype "passive"))
    )
    (net (code "62") (name "VCC_IN_1") (class "Default")
      (node (ref "C33") (pin "2") (pinfunction "2_2") (pintype "passive"))
      (node (ref "J1") (pin "1") (pinfunction "0_1") (pintype "passive"))
      (node (ref "L3") (pin "1") (pinfunction "1_1") (pintype "passive"))
    )
    (net (code "63") (name "VCC_IN_2") (class "Default")
      (node (ref "C32") (pin "1") (pinfunction "1_1") (pintype "passive"))
      (node (ref "J6") (pin "1") (pinfunction "0_1") (pintype "passive"))
      (node (ref "L3") (pin "5") (pinfunction "5_5") (pintype "passive"))
    )
    (net (code "64") (name "VCC_ISO") (class "Default")
      (node (ref "DA1") (pin "3") (pinfunction "VCC_3") (pintype "passive"))
      (node (ref "DA2") (pin "3") (pinfunction "VCC_3") (pintype "passive"))
      (node (ref "X1") (pin "10") (pinfunction "10_10") (pintype "passive"))
    )
    (net (code "65") (name "VCC_OUT") (class "Default")
      (node (ref "C10") (pin "2") (pinfunction "2_2") (pintype "passive"))
      (node (ref "C11") (pin "2") (pinfunction "2_2") (pintype "passive"))
      (node (ref "C12") (pin "2") (pinfunction "2_2") (pintype "passive"))
      (node (ref "J4") (pin "1") (pinfunction "0_1") (pintype "passive"))
      (node (ref "VD3") (pin "1") (pinfunction "1_1") (pintype "passive"))
      (node (ref "VD4") (pin "1") (pinfunction "1_1") (pintype "passive"))
    )
    (net (code "66") (name "VCC_OUT_2") (class "Default")
      (node (ref "J7") (pin "3") (pinfunction "3_3") (pintype "passive"))
      (node (ref "VD1") (pin "1") (pinfunction "C_1") (pintype "passive"))
      (node (ref "VD2") (pin "1") (pinfunction "C_1") (pintype "passive"))
    )
    (net (code "67") (name "VCC_SENS") (class "Default")
      (node (ref "C13") (pin "1") (pinfunction "+_1") (pintype "passive"))
      (node (ref "C14") (pin "1") (pinfunction "1_1") (pintype "passive"))
      (node (ref "C17") (pin "1") (pinfunction "1_1") (pintype "passive"))
      (node (ref "C19") (pin "1") (pinfunction "1_1") (pintype "passive"))
      (node (ref "C2") (pin "1") (pinfunction "+_1") (pintype "passive"))
      (node (ref "C22") (pin "1") (pinfunction "1_1") (pintype "passive"))
      (node (ref "DA3") (pin "8") (pinfunction "VCC_8") (pintype "passive"))
      (node (ref "DA4") (pin "8") (pinfunction "VCC_8") (pintype "passive"))
      (node (ref "T1") (pin "3") (pinfunction "VCC+_3") (pintype "passive"))
      (node (ref "T2") (pin "3") (pinfunction "VCC+_3") (pintype "passive"))
      (node (ref "X1") (pin "8") (pinfunction "8_8") (pintype "passive"))
    )
    (net (code "68") (name "unconnected-(DA1-NC-Pad6)") (class "Default")
      (node (ref "DA1") (pin "6") (pinfunction "NC_6") (pintype "passive"))
    )
    (net (code "69") (name "unconnected-(DA2-NC-Pad6)") (class "Default")
      (node (ref "DA2") (pin "6") (pinfunction "NC_6") (pintype "passive"))
    )
    (net (code "70") (name "unconnected-(J7-Pad2)") (class "Default")
      (node (ref "J7") (pin "2") (pinfunction "2_2") (pintype "passive"))
    )
    (net (code "71") (name "unconnected-(X1-Pad12)") (class "Default")
      (node (ref "X1") (pin "12") (pinfunction "12_12") (pintype "passive"))
    )
  )
)
